# ThoraxSensor3_0_6_2024_VCNT2020.net
KiCad netlist of a schematic drawn in EAGLE
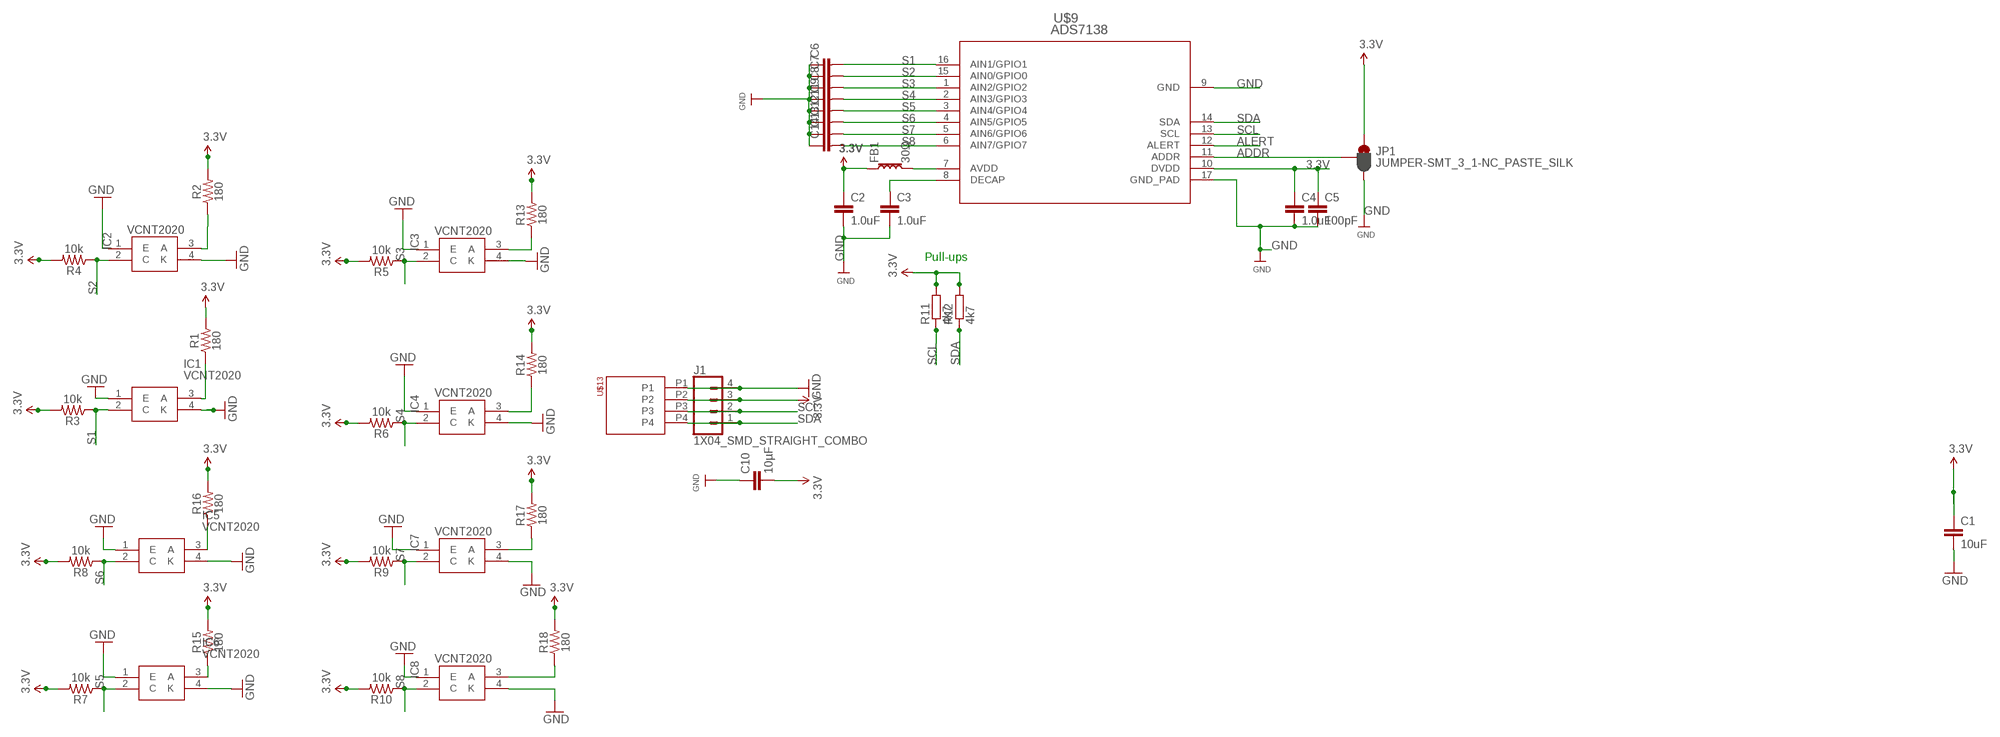
[diagram p0: schematic, sheet 1]

(export (version "E")
  (design (tool "Eeschema 10.0.6"))
  (components
    (comp (ref "C1")
      (value "10uF")
      (footprint "eagle-import:0805")
      (libsource (lib "eagle-import") (part "10UF-0805-10V-10%"))
    )
    (comp (ref "C2")
      (value "1.0uF")
      (footprint "eagle-import:0603")
      (libsource (lib "eagle-import") (part "1.0UF-0603-16V-10%"))
    )
    (comp (ref "C3")
      (value "1.0uF")
      (footprint "eagle-import:0603")
      (libsource (lib "eagle-import") (part "1.0UF-0603-16V-10%"))
    )
    (comp (ref "C4")
      (value "1.0uF")
      (footprint "eagle-import:0603")
      (libsource (lib "eagle-import") (part "1.0UF-0603-16V-10%"))
    )
    (comp (ref "C5")
      (value "100pF")
      (footprint "eagle-import:0603")
      (libsource (lib "eagle-import") (part "100PF-0603-50V-5%"))
    )
    (comp (ref "C6")
      (value "0.1uF")
      (footprint "eagle-import:0603")
      (libsource (lib "eagle-import") (part "CAP_CERAMIC0603"))
    )
    (comp (ref "C7")
      (value "0.1uF")
      (footprint "eagle-import:0603")
      (libsource (lib "eagle-import") (part "CAP_CERAMIC0603"))
    )
    (comp (ref "C8")
      (value "0.1uF")
      (footprint "eagle-import:0603")
      (libsource (lib "eagle-import") (part "CAP_CERAMIC0603"))
    )
    (comp (ref "C9")
      (value "0.1uF")
      (footprint "eagle-import:0603")
      (libsource (lib "eagle-import") (part "CAP_CERAMIC0603"))
    )
    (comp (ref "C10")
      (value "10µF")
      (footprint "eagle-import:C0805")
      (libsource (lib "eagle-import") (part "C-EUC0805"))
    )
    (comp (ref "C11")
      (value "0.1uF")
      (footprint "eagle-import:0603")
      (libsource (lib "eagle-import") (part "CAP_CERAMIC0603"))
    )
    (comp (ref "C12")
      (value "0.1uF")
      (footprint "eagle-import:0603")
      (libsource (lib "eagle-import") (part "CAP_CERAMIC0603"))
    )
    (comp (ref "C13")
      (value "0.1uF")
      (footprint "eagle-import:0603")
      (libsource (lib "eagle-import") (part "CAP_CERAMIC0603"))
    )
    (comp (ref "C14")
      (value "0.1uF")
      (footprint "eagle-import:0603")
      (libsource (lib "eagle-import") (part "CAP_CERAMIC0603"))
    )
    (comp (ref "FB1")
      (value "30Ω")
      (footprint "eagle-import:0603")
      (libsource (lib "eagle-import") (part "FERRITE_BEAD-0603-30Ω-100MHZ"))
    )
    (comp (ref "IC1")
      (value "VCNT2020")
      (footprint "eagle-import:VCNT2020")
      (fields (field (name "MOUSER_PART_NUMBER") "78-VCNT2020"))
      (libsource (lib "eagle-import") (part "VCNT2020"))
    )
    (comp (ref "IC2")
      (value "VCNT2020")
      (footprint "eagle-import:VCNT2020")
      (fields (field (name "MOUSER_PART_NUMBER") "78-VCNT2020"))
      (libsource (lib "eagle-import") (part "VCNT2020"))
    )
    (comp (ref "IC3")
      (value "VCNT2020")
      (footprint "eagle-import:VCNT2020")
      (fields (field (name "MOUSER_PART_NUMBER") "78-VCNT2020"))
      (libsource (lib "eagle-import") (part "VCNT2020"))
    )
    (comp (ref "IC4")
      (value "VCNT2020")
      (footprint "eagle-import:VCNT2020")
      (fields (field (name "MOUSER_PART_NUMBER") "78-VCNT2020"))
      (libsource (lib "eagle-import") (part "VCNT2020"))
    )
    (comp (ref "IC5")
      (value "VCNT2020")
      (footprint "eagle-import:VCNT2020")
      (fields (field (name "MOUSER_PART_NUMBER") "78-VCNT2020"))
      (libsource (lib "eagle-import") (part "VCNT2020"))
    )
    (comp (ref "IC6")
      (value "VCNT2020")
      (footprint "eagle-import:VCNT2020")
      (fields (field (name "MOUSER_PART_NUMBER") "78-VCNT2020"))
      (libsource (lib "eagle-import") (part "VCNT2020"))
    )
    (comp (ref "IC7")
      (value "VCNT2020")
      (footprint "eagle-import:VCNT2020")
      (fields (field (name "MOUSER_PART_NUMBER") "78-VCNT2020"))
      (libsource (lib "eagle-import") (part "VCNT2020"))
    )
    (comp (ref "IC8")
      (value "VCNT2020")
      (footprint "eagle-import:VCNT2020")
      (fields (field (name "MOUSER_PART_NUMBER") "78-VCNT2020"))
      (libsource (lib "eagle-import") (part "VCNT2020"))
    )
    (comp (ref "J1")
      (value "1X04_SMD_STRAIGHT_COMBO")
      (footprint "eagle-import:1X04_SMD_VERTICAL_COMBO")
      (libsource (lib "eagle-import") (part "CONN_04SMD_STRAIGHT_COMBO"))
    )
    (comp (ref "JP1")
      (value "JUMPER-SMT_3_1-NC_PASTE_SILK")
      (footprint "eagle-import:SMT-JUMPER_3_1-NC_PASTE_SILK")
      (libsource (lib "eagle-import") (part "JUMPER-SMT_3_1-NC_PASTE_SILK"))
    )
    (comp (ref "R1")
      (value "180")
      (footprint "eagle-import:0603")
      (libsource (lib "eagle-import") (part "180OHM-0603-1/10W-1%"))
    )
    (comp (ref "R2")
      (value "180")
      (footprint "eagle-import:0603")
      (libsource (lib "eagle-import") (part "180OHM-0603-1/10W-1%"))
    )
    (comp (ref "R3")
      (value "10k")
      (footprint "eagle-import:0603")
      (libsource (lib "eagle-import") (part "10KOHM-0603-1/10W-1%"))
    )
    (comp (ref "R4")
      (value "10k")
      (footprint "eagle-import:0603")
      (libsource (lib "eagle-import") (part "10KOHM-0603-1/10W-1%"))
    )
    (comp (ref "R5")
      (value "10k")
      (footprint "eagle-import:0603")
      (libsource (lib "eagle-import") (part "10KOHM-0603-1/10W-1%"))
    )
    (comp (ref "R6")
      (value "10k")
      (footprint "eagle-import:0603")
      (libsource (lib "eagle-import") (part "10KOHM-0603-1/10W-1%"))
    )
    (comp (ref "R7")
      (value "10k")
      (footprint "eagle-import:0603")
      (libsource (lib "eagle-import") (part "10KOHM-0603-1/10W-1%"))
    )
    (comp (ref "R8")
      (value "10k")
      (footprint "eagle-import:0603")
      (libsource (lib "eagle-import") (part "10KOHM-0603-1/10W-1%"))
    )
    (comp (ref "R9")
      (value "10k")
      (footprint "eagle-import:0603")
      (libsource (lib "eagle-import") (part "10KOHM-0603-1/10W-1%"))
    )
    (comp (ref "R10")
      (value "10k")
      (footprint "eagle-import:0603")
      (libsource (lib "eagle-import") (part "10KOHM-0603-1/10W-1%"))
    )
    (comp (ref "R11")
      (value "4k7")
      (footprint "eagle-import:R0603")
      (libsource (lib "eagle-import") (part "R-EU_R0603"))
    )
    (comp (ref "R12")
      (value "4k7")
      (footprint "eagle-import:R0603")
      (libsource (lib "eagle-import") (part "R-EU_R0603"))
    )
    (comp (ref "R13")
      (value "180")
      (footprint "eagle-import:0603")
      (libsource (lib "eagle-import") (part "180OHM-0603-1/10W-1%"))
    )
    (comp (ref "R14")
      (value "180")
      (footprint "eagle-import:0603")
      (libsource (lib "eagle-import") (part "180OHM-0603-1/10W-1%"))
    )
    (comp (ref "R15")
      (value "180")
      (footprint "eagle-import:0603")
      (libsource (lib "eagle-import") (part "180OHM-0603-1/10W-1%"))
    )
    (comp (ref "R16")
      (value "180")
      (footprint "eagle-import:0603")
      (libsource (lib "eagle-import") (part "180OHM-0603-1/10W-1%"))
    )
    (comp (ref "R17")
      (value "180")
      (footprint "eagle-import:0603")
      (libsource (lib "eagle-import") (part "180OHM-0603-1/10W-1%"))
    )
    (comp (ref "R18")
      (value "180")
      (footprint "eagle-import:0603")
      (libsource (lib "eagle-import") (part "180OHM-0603-1/10W-1%"))
    )
    (comp (ref "U$9")
      (value "ADS7138")
      (footprint "eagle-import:QFN_8IRTER_TEX")
      (libsource (lib "eagle-import") (part "ADS7138"))
    )
    (comp (ref "U$13")
      (value "PHOENIX_PTSM_M4_TH_ANGLEMIRRORED_SILK_I2C")
      (footprint "eagle-import:PTSM_M4_TH_ANGLE_NEUTRAL_MIRRORED")
      (libsource (lib "eagle-import") (part "PHOENIX_PTSM_M4_TH_ANGLEMIRRORED_SILK_I2C"))
    )
  )
  (nets
    (net (code "1") (name "/ADDR") (class "Default")
      (node (ref "JP1") (pin "2") (pinfunction "2_2") (pintype "passive"))
      (node (ref "U$9") (pin "11") (pinfunction "ADDR_11") (pintype "passive"))
    )
    (net (code "2") (name "/ALERT") (class "Default")
      (node (ref "U$9") (pin "12") (pinfunction "ALERT_12") (pintype "passive"))
    )
    (net (code "3") (name "/S1") (class "Default")
      (node (ref "C6") (pin "2") (pinfunction "P$2_2") (pintype "passive"))
      (node (ref "IC1") (pin "2") (pinfunction "C_2") (pintype "bidirectional"))
      (node (ref "R3") (pin "1") (pinfunction "1_1") (pintype "passive"))
      (node (ref "U$9") (pin "16") (pinfunction "AIN1/GPIO1_16") (pintype "passive"))
    )
    (net (code "4") (name "/S2") (class "Default")
      (node (ref "C7") (pin "2") (pinfunction "P$2_2") (pintype "passive"))
      (node (ref "IC2") (pin "2") (pinfunction "C_2") (pintype "bidirectional"))
      (node (ref "R4") (pin "1") (pinfunction "1_1") (pintype "passive"))
      (node (ref "U$9") (pin "15") (pinfunction "AIN0/GPIO0_15") (pintype "passive"))
    )
    (net (code "5") (name "/S3") (class "Default")
      (node (ref "C8") (pin "2") (pinfunction "P$2_2") (pintype "passive"))
      (node (ref "IC3") (pin "2") (pinfunction "C_2") (pintype "bidirectional"))
      (node (ref "R5") (pin "1") (pinfunction "1_1") (pintype "passive"))
      (node (ref "U$9") (pin "1") (pinfunction "AIN2/GPIO2_1") (pintype "passive"))
    )
    (net (code "6") (name "/S4") (class "Default")
      (node (ref "C9") (pin "2") (pinfunction "P$2_2") (pintype "passive"))
      (node (ref "IC4") (pin "2") (pinfunction "C_2") (pintype "bidirectional"))
      (node (ref "R6") (pin "1") (pinfunction "1_1") (pintype "passive"))
      (node (ref "U$9") (pin "2") (pinfunction "AIN3/GPIO3_2") (pintype "passive"))
    )
    (net (code "7") (name "/S5") (class "Default")
      (node (ref "C11") (pin "2") (pinfunction "P$2_2") (pintype "passive"))
      (node (ref "IC6") (pin "2") (pinfunction "C_2") (pintype "bidirectional"))
      (node (ref "R7") (pin "1") (pinfunction "1_1") (pintype "passive"))
      (node (ref "U$9") (pin "3") (pinfunction "AIN4/GPIO4_3") (pintype "passive"))
    )
    (net (code "8") (name "/S6") (class "Default")
      (node (ref "C12") (pin "2") (pinfunction "P$2_2") (pintype "passive"))
      (node (ref "IC5") (pin "2") (pinfunction "C_2") (pintype "bidirectional"))
      (node (ref "R8") (pin "1") (pinfunction "1_1") (pintype "passive"))
      (node (ref "U$9") (pin "4") (pinfunction "AIN5/GPIO5_4") (pintype "passive"))
    )
    (net (code "9") (name "/S7") (class "Default")
      (node (ref "C13") (pin "2") (pinfunction "P$2_2") (pintype "passive"))
      (node (ref "IC7") (pin "2") (pinfunction "C_2") (pintype "bidirectional"))
      (node (ref "R9") (pin "1") (pinfunction "1_1") (pintype "passive"))
      (node (ref "U$9") (pin "5") (pinfunction "AIN6/GPIO6_5") (pintype "passive"))
    )
    (net (code "10") (name "/S8") (class "Default")
      (node (ref "C14") (pin "2") (pinfunction "P$2_2") (pintype "passive"))
      (node (ref "IC8") (pin "2") (pinfunction "C_2") (pintype "bidirectional"))
      (node (ref "R10") (pin "1") (pinfunction "1_1") (pintype "passive"))
      (node (ref "U$9") (pin "6") (pinfunction "AIN7/GPIO7_6") (pintype "passive"))
    )
    (net (code "11") (name "/SCL") (class "Default")
      (node (ref "J1") (pin "2") (pinfunction "2_2") (pintype "passive"))
      (node (ref "R11") (pin "1") (pinfunction "1_1") (pintype "passive"))
      (node (ref "U$13") (pin "P3") (pinfunction "P3_P3") (pintype "power_in"))
      (node (ref "U$9") (pin "13") (pinfunction "SCL_13") (pintype "passive"))
    )
    (net (code "12") (name "/SDA") (class "Default")
      (node (ref "J1") (pin "1") (pinfunction "1_1") (pintype "passive"))
      (node (ref "R12") (pin "1") (pinfunction "1_1") (pintype "passive"))
      (node (ref "U$13") (pin "P4") (pinfunction "P4_P4") (pintype "power_in"))
      (node (ref "U$9") (pin "14") (pinfunction "SDA_14") (pintype "passive"))
    )
    (net (code "13") (name "3.3V") (class "Default")
      (node (ref "C1") (pin "1") (pinfunction "1_1") (pintype "passive"))
      (node (ref "C10") (pin "2") (pinfunction "2_2") (pintype "passive"))
      (node (ref "C2") (pin "1") (pinfunction "1_1") (pintype "passive"))
      (node (ref "C4") (pin "1") (pinfunction "1_1") (pintype "passive"))
      (node (ref "C5") (pin "1") (pinfunction "1_1") (pintype "passive"))
      (node (ref "FB1") (pin "1") (pinfunction "1_1") (pintype "passive"))
      (node (ref "J1") (pin "3") (pinfunction "3_3") (pintype "passive"))
      (node (ref "JP1") (pin "1") (pinfunction "1_1") (pintype "passive"))
      (node (ref "R1") (pin "2") (pinfunction "2_2") (pintype "passive"))
      (node (ref "R10") (pin "2") (pinfunction "2_2") (pintype "passive"))
      (node (ref "R11") (pin "2") (pinfunction "2_2") (pintype "passive"))
      (node (ref "R12") (pin "2") (pinfunction "2_2") (pintype "passive"))
      (node (ref "R13") (pin "2") (pinfunction "2_2") (pintype "passive"))
      (node (ref "R14") (pin "2") (pinfunction "2_2") (pintype "passive"))
      (node (ref "R15") (pin "2") (pinfunction "2_2") (pintype "passive"))
      (node (ref "R16") (pin "2") (pinfunction "2_2") (pintype "passive"))
      (node (ref "R17") (pin "2") (pinfunction "2_2") (pintype "passive"))
      (node (ref "R18") (pin "2") (pinfunction "2_2") (pintype "passive"))
      (node (ref "R2") (pin "2") (pinfunction "2_2") (pintype "passive"))
      (node (ref "R3") (pin "2") (pinfunction "2_2") (pintype "passive"))
      (node (ref "R4") (pin "2") (pinfunction "2_2") (pintype "passive"))
      (node (ref "R5") (pin "2") (pinfunction "2_2") (pintype "passive"))
      (node (ref "R6") (pin "2") (pinfunction "2_2") (pintype "passive"))
      (node (ref "R7") (pin "2") (pinfunction "2_2") (pintype "passive"))
      (node (ref "R8") (pin "2") (pinfunction "2_2") (pintype "passive"))
      (node (ref "R9") (pin "2") (pinfunction "2_2") (pintype "passive"))
      (node (ref "U$13") (pin "P2") (pinfunction "P2_P2") (pintype "power_in"))
      (node (ref "U$9") (pin "10") (pinfunction "DVDD_10") (pintype "passive"))
    )
    (net (code "14") (name "GND") (class "Default")
      (node (ref "C1") (pin "2") (pinfunction "2_2") (pintype "passive"))
      (node (ref "C10") (pin "1") (pinfunction "1_1") (pintype "passive"))
      (node (ref "C11") (pin "1") (pinfunction "P$1_1") (pintype "passive"))
      (node (ref "C12") (pin "1") (pinfunction "P$1_1") (pintype "passive"))
      (node (ref "C13") (pin "1") (pinfunction "P$1_1") (pintype "passive"))
      (node (ref "C14") (pin "1") (pinfunction "P$1_1") (pintype "passive"))
      (node (ref "C2") (pin "2") (pinfunction "2_2") (pintype "passive"))
      (node (ref "C3") (pin "2") (pinfunction "2_2") (pintype "passive"))
      (node (ref "C4") (pin "2") (pinfunction "2_2") (pintype "passive"))
      (node (ref "C5") (pin "2") (pinfunction "2_2") (pintype "passive"))
      (node (ref "C6") (pin "1") (pinfunction "P$1_1") (pintype "passive"))
      (node (ref "C7") (pin "1") (pinfunction "P$1_1") (pintype "passive"))
      (node (ref "C8") (pin "1") (pinfunction "P$1_1") (pintype "passive"))
      (node (ref "C9") (pin "1") (pinfunction "P$1_1") (pintype "passive"))
      (node (ref "IC1") (pin "1") (pinfunction "E_1") (pintype "bidirectional"))
      (node (ref "IC1") (pin "4") (pinfunction "K_4") (pintype "bidirectional"))
      (node (ref "IC2") (pin "1") (pinfunction "E_1") (pintype "bidirectional"))
      (node (ref "IC2") (pin "4") (pinfunction "K_4") (pintype "bidirectional"))
      (node (ref "IC3") (pin "1") (pinfunction "E_1") (pintype "bidirectional"))
      (node (ref "IC3") (pin "4") (pinfunction "K_4") (pintype "bidirectional"))
      (node (ref "IC4") (pin "1") (pinfunction "E_1") (pintype "bidirectional"))
      (node (ref "IC4") (pin "4") (pinfunction "K_4") (pintype "bidirectional"))
      (node (ref "IC5") (pin "1") (pinfunction "E_1") (pintype "bidirectional"))
      (node (ref "IC5") (pin "4") (pinfunction "K_4") (pintype "bidirectional"))
      (node (ref "IC6") (pin "1") (pinfunction "E_1") (pintype "bidirectional"))
      (node (ref "IC6") (pin "4") (pinfunction "K_4") (pintype "bidirectional"))
      (node (ref "IC7") (pin "1") (pinfunction "E_1") (pintype "bidirectional"))
      (node (ref "IC7") (pin "4") (pinfunction "K_4") (pintype "bidirectional"))
      (node (ref "IC8") (pin "1") (pinfunction "E_1") (pintype "bidirectional"))
      (node (ref "IC8") (pin "4") (pinfunction "K_4") (pintype "bidirectional"))
      (node (ref "J1") (pin "4") (pinfunction "4_4") (pintype "passive"))
      (node (ref "JP1") (pin "3") (pinfunction "3_3") (pintype "passive"))
      (node (ref "U$13") (pin "P1") (pinfunction "P1_P1") (pintype "power_in"))
      (node (ref "U$9") (pin "17") (pinfunction "GND_PAD_17") (pintype "passive"))
      (node (ref "U$9") (pin "9") (pinfunction "GND_9") (pintype "passive"))
    )
    (net (code "15") (name "Net-(IC1-A)") (class "Default")
      (node (ref "IC1") (pin "3") (pinfunction "A_3") (pintype "bidirectional"))
      (node (ref "R1") (pin "1") (pinfunction "1_1") (pintype "passive"))
    )
    (net (code "16") (name "Net-(IC2-A)") (class "Default")
      (node (ref "IC2") (pin "3") (pinfunction "A_3") (pintype "bidirectional"))
      (node (ref "R2") (pin "1") (pinfunction "1_1") (pintype "passive"))
    )
    (net (code "17") (name "Net-(IC3-A)") (class "Default")
      (node (ref "IC3") (pin "3") (pinfunction "A_3") (pintype "bidirectional"))
      (node (ref "R13") (pin "1") (pinfunction "1_1") (pintype "passive"))
    )
    (net (code "18") (name "Net-(IC4-A)") (class "Default")
      (node (ref "IC4") (pin "3") (pinfunction "A_3") (pintype "bidirectional"))
      (node (ref "R14") (pin "1") (pinfunction "1_1") (pintype "passive"))
    )
    (net (code "19") (name "Net-(IC5-A)") (class "Default")
      (node (ref "IC5") (pin "3") (pinfunction "A_3") (pintype "bidirectional"))
      (node (ref "R16") (pin "1") (pinfunction "1_1") (pintype "passive"))
    )
    (net (code "20") (name "Net-(IC6-A)") (class "Default")
      (node (ref "IC6") (pin "3") (pinfunction "A_3") (pintype "bidirectional"))
      (node (ref "R15") (pin "1") (pinfunction "1_1") (pintype "passive"))
    )
    (net (code "21") (name "Net-(IC7-A)") (class "Default")
      (node (ref "IC7") (pin "3") (pinfunction "A_3") (pintype "bidirectional"))
      (node (ref "R17") (pin "1") (pinfunction "1_1") (pintype "passive"))
    )
    (net (code "22") (name "Net-(IC8-A)") (class "Default")
      (node (ref "IC8") (pin "3") (pinfunction "A_3") (pintype "bidirectional"))
      (node (ref "R18") (pin "1") (pinfunction "1_1") (pintype "passive"))
    )
    (net (code "23") (name "Net-(U$9-AVDD)") (class "Default")
      (node (ref "FB1") (pin "2") (pinfunction "2_2") (pintype "passive"))
      (node (ref "U$9") (pin "7") (pinfunction "AVDD_7") (pintype "passive"))
    )
    (net (code "24") (name "Net-(U$9-DECAP)") (class "Default")
      (node (ref "C3") (pin "1") (pinfunction "1_1") (pintype "passive"))
      (node (ref "U$9") (pin "8") (pinfunction "DECAP_8") (pintype "passive"))
    )
  )
)
